# MAX96717_PINOUT.net
KiCad netlist of a schematic drawn in Altium Designer
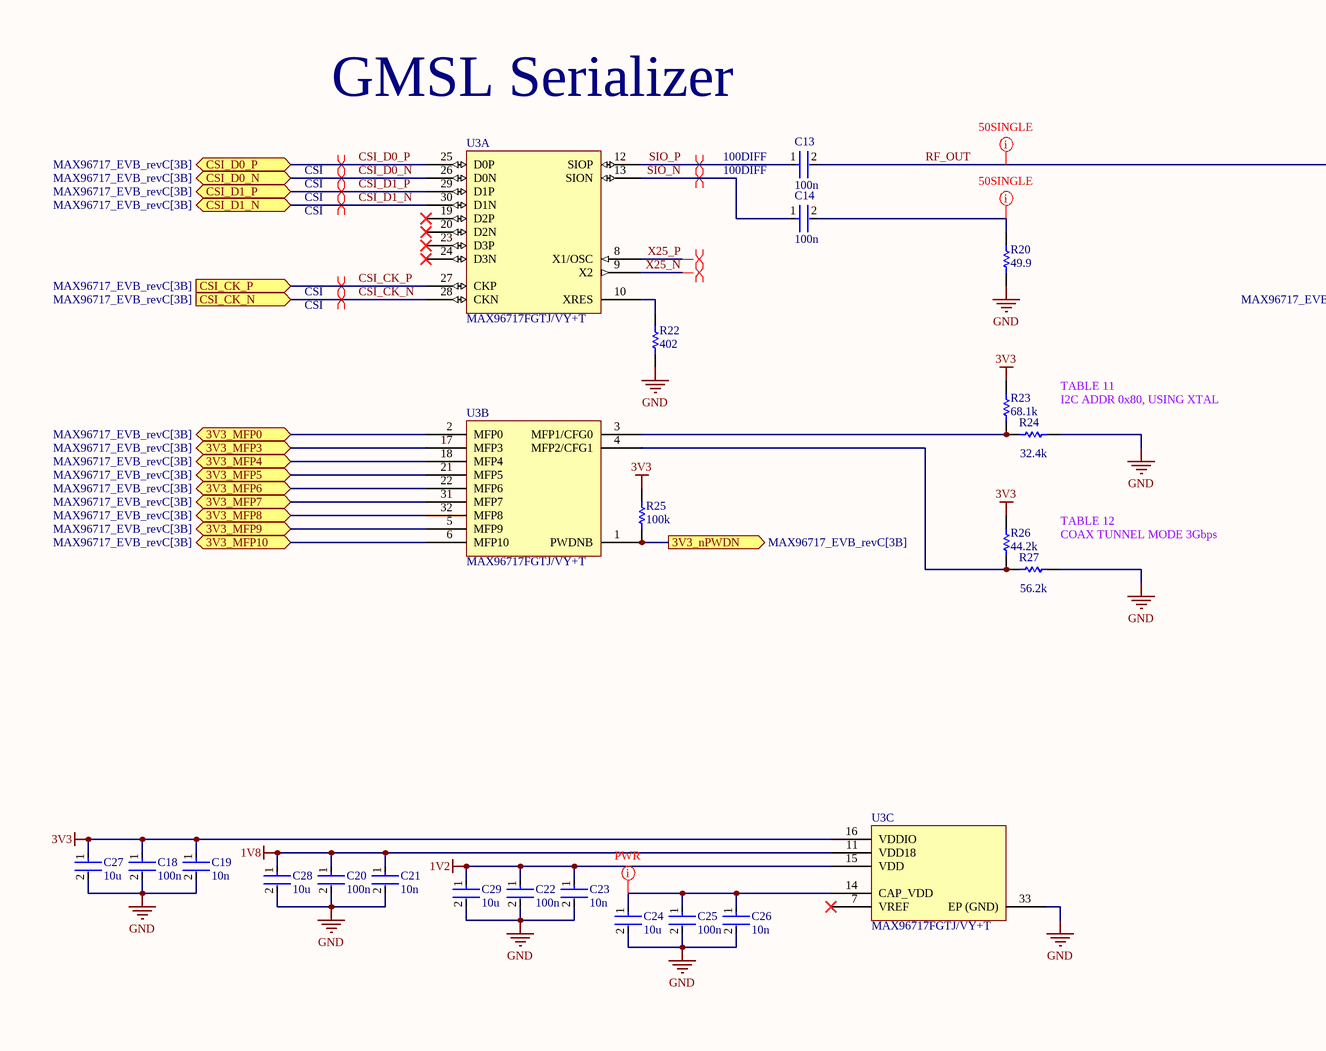
[diagram p0: MAX96717_PINOUT.SchDoc, left]
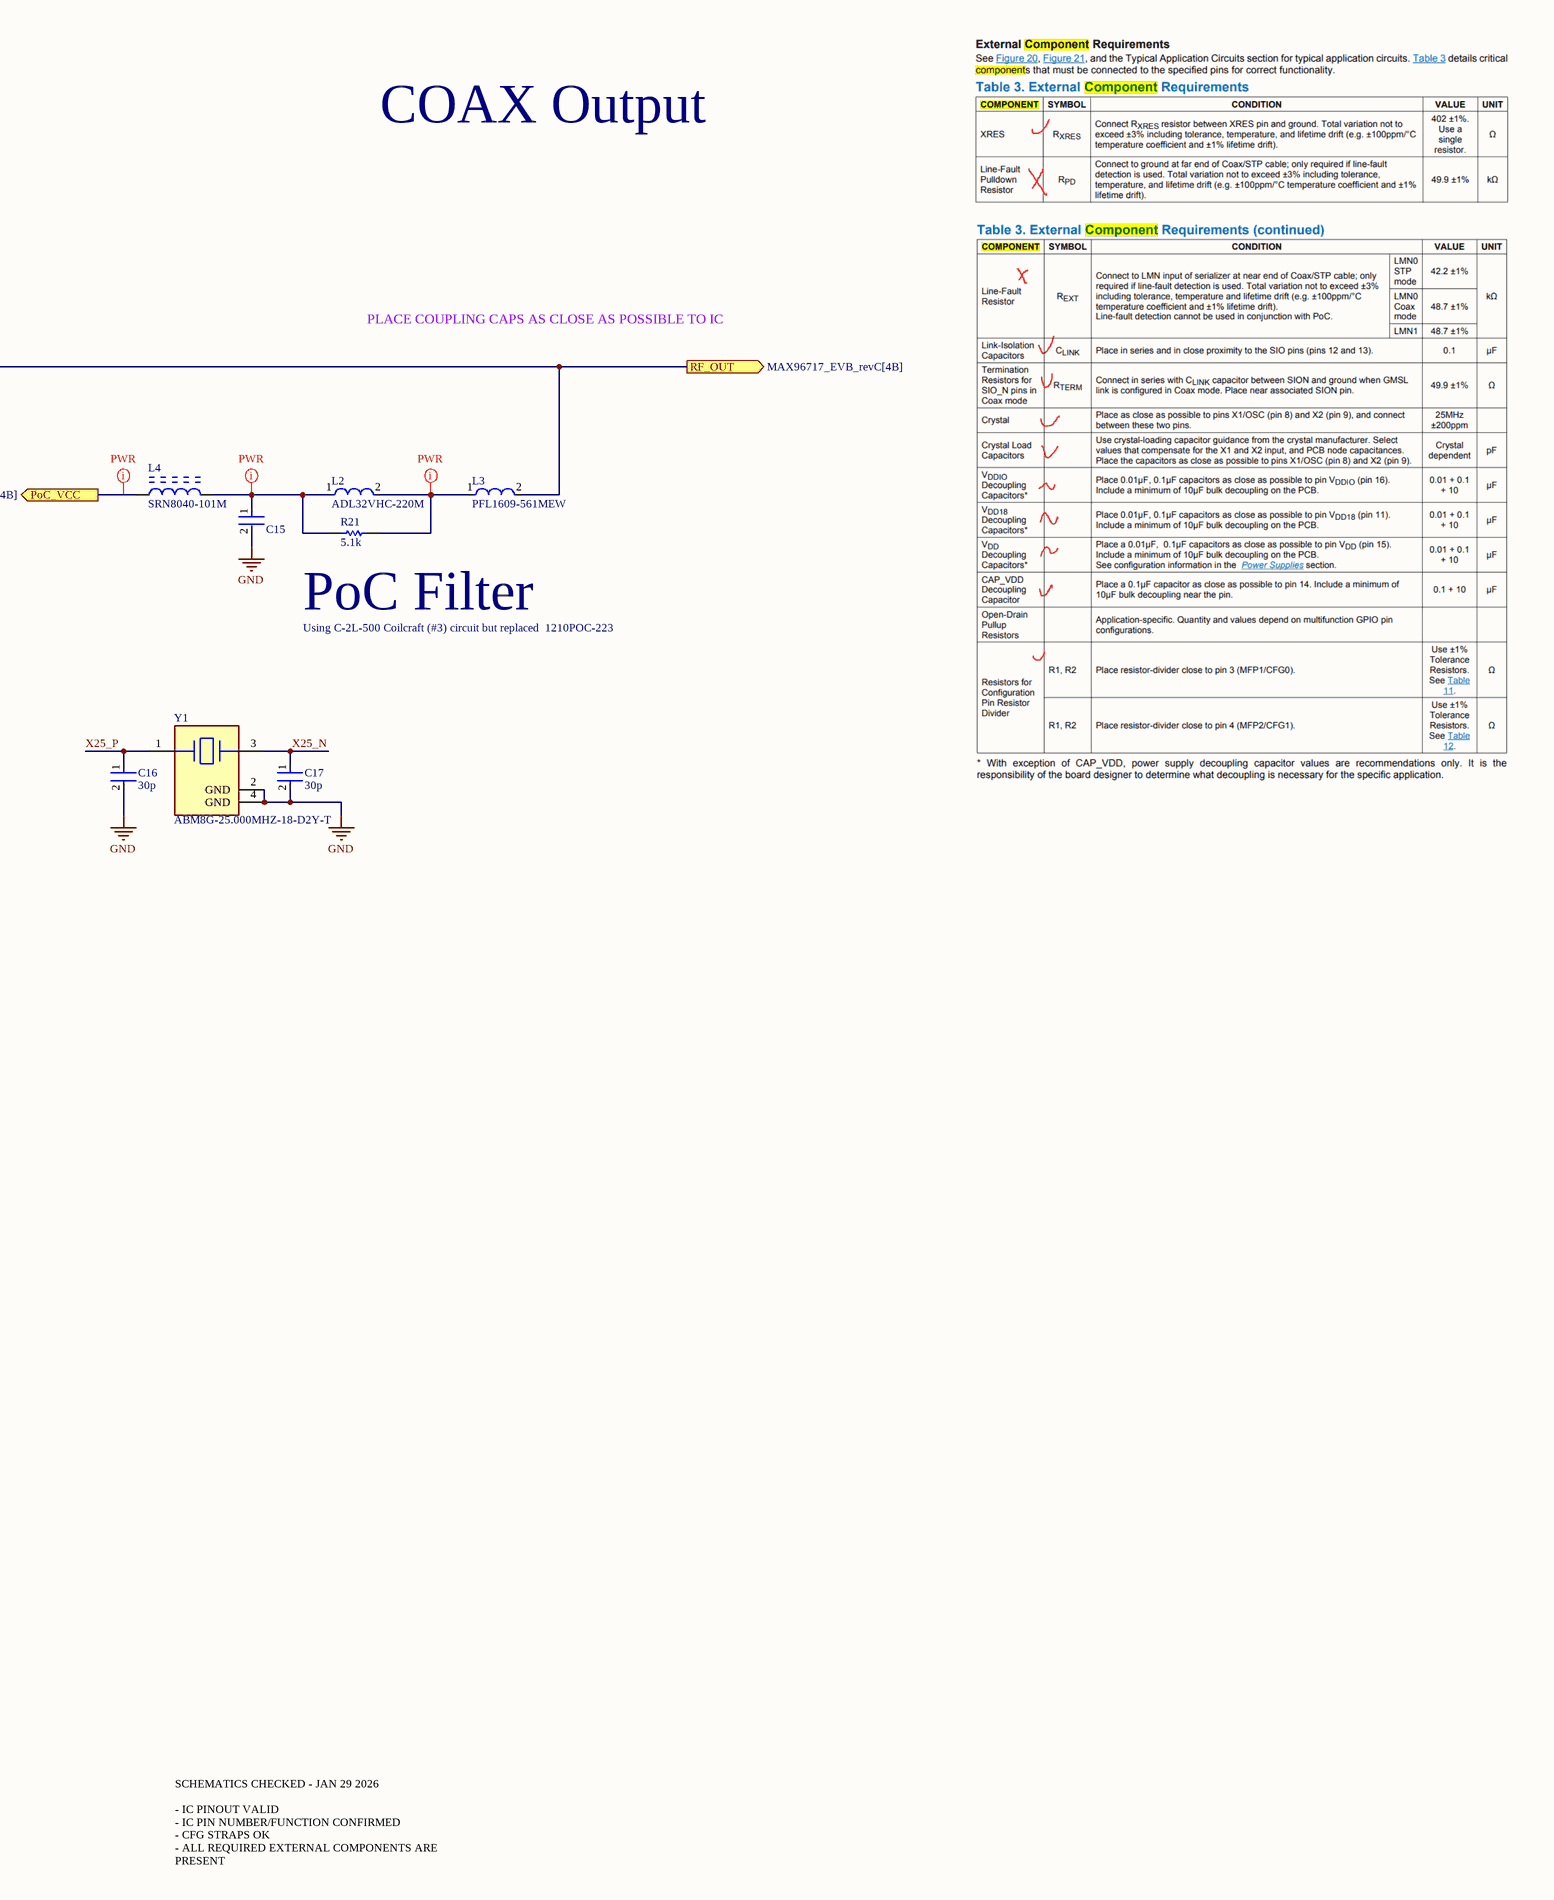
[diagram p1: MAX96717_PINOUT.SchDoc, right]

(export (version "E")
  (design (tool "Eeschema 10.0.6"))
  (components
    (comp (ref "C13")
      (value "100n")
      (footprint "FP-0402-L_1_0_0_05-W_0_5-IPC_A")
      (description "LARGE PADS, 0402 CAP, CHANGE COMMENT TO MATCH REAL P/N")
      (libsource (lib "Space Concordia") (part "b4654b650e69147ec39a6b967a45e02"))
    )
    (comp (ref "C14")
      (value "100n")
      (footprint "FP-0402-L_1_0_0_05-W_0_5-IPC_A")
      (description "LARGE PADS, 0402 CAP, CHANGE COMMENT TO MATCH REAL P/N")
      (libsource (lib "Space Concordia") (part "b4654b650e69147ec39a6b967a45e02"))
    )
    (comp (ref "C15")
      (value "GRM21BR61E226ME44L")
      (footprint "FP-GRM21B-0_2-e0_2_0_7-IPC_B")
      (description "Chip Multilayer Ceramic Capacitors for General Purpose, 0805, 22uF, X5R, 15%, 20%, 25V")
      (fields (field (name "TOLERANCE") "20%") (field (name "VOLTAGE") "25V"))
      (libsource (lib "Altium Content Vault") (part "b4654b650e69147ec39a6b967a45e02"))
    )
    (comp (ref "C16")
      (value "30p")
      (footprint "FP-0402-L_1_0_0_05-W_0_5-IPC_A")
      (description "LARGE PADS, 0402 CAP, CHANGE COMMENT TO MATCH REAL P/N")
      (libsource (lib "Space Concordia") (part "b4654b650e69147ec39a6b967a45e02"))
    )
    (comp (ref "C17")
      (value "30p")
      (footprint "FP-0402-L_1_0_0_05-W_0_5-IPC_A")
      (description "LARGE PADS, 0402 CAP, CHANGE COMMENT TO MATCH REAL P/N")
      (libsource (lib "Space Concordia") (part "b4654b650e69147ec39a6b967a45e02"))
    )
    (comp (ref "C18")
      (value "100n")
      (footprint "FP-0402-L_1_0_0_05-W_0_5-IPC_A")
      (description "LARGE PADS, 0402 CAP, CHANGE COMMENT TO MATCH REAL P/N")
      (libsource (lib "Space Concordia") (part "b4654b650e69147ec39a6b967a45e02"))
    )
    (comp (ref "C19")
      (value "10n")
      (footprint "FP-0402-L_1_0_0_05-W_0_5-IPC_A")
      (description "LARGE PADS, 0402 CAP, CHANGE COMMENT TO MATCH REAL P/N")
      (libsource (lib "Space Concordia") (part "b4654b650e69147ec39a6b967a45e02"))
    )
    (comp (ref "C20")
      (value "100n")
      (footprint "FP-0402-L_1_0_0_05-W_0_5-IPC_A")
      (description "LARGE PADS, 0402 CAP, CHANGE COMMENT TO MATCH REAL P/N")
      (libsource (lib "Space Concordia") (part "b4654b650e69147ec39a6b967a45e02"))
    )
    (comp (ref "C21")
      (value "10n")
      (footprint "FP-0402-L_1_0_0_05-W_0_5-IPC_A")
      (description "LARGE PADS, 0402 CAP, CHANGE COMMENT TO MATCH REAL P/N")
      (libsource (lib "Space Concordia") (part "b4654b650e69147ec39a6b967a45e02"))
    )
    (comp (ref "C22")
      (value "100n")
      (footprint "FP-0402-L_1_0_0_05-W_0_5-IPC_A")
      (description "LARGE PADS, 0402 CAP, CHANGE COMMENT TO MATCH REAL P/N")
      (libsource (lib "Space Concordia") (part "b4654b650e69147ec39a6b967a45e02"))
    )
    (comp (ref "C23")
      (value "10n")
      (footprint "FP-0402-L_1_0_0_05-W_0_5-IPC_A")
      (description "LARGE PADS, 0402 CAP, CHANGE COMMENT TO MATCH REAL P/N")
      (libsource (lib "Space Concordia") (part "b4654b650e69147ec39a6b967a45e02"))
    )
    (comp (ref "C24")
      (value "10u")
      (footprint "FP-0402-L_1_0_0_05-W_0_5-IPC_A")
      (description "LARGE PADS, 0402 CAP, CHANGE COMMENT TO MATCH REAL P/N")
      (libsource (lib "Space Concordia") (part "b4654b650e69147ec39a6b967a45e02"))
    )
    (comp (ref "C25")
      (value "100n")
      (footprint "FP-0402-L_1_0_0_05-W_0_5-IPC_A")
      (description "LARGE PADS, 0402 CAP, CHANGE COMMENT TO MATCH REAL P/N")
      (libsource (lib "Space Concordia") (part "b4654b650e69147ec39a6b967a45e02"))
    )
    (comp (ref "C26")
      (value "10n")
      (footprint "FP-0402-L_1_0_0_05-W_0_5-IPC_A")
      (description "LARGE PADS, 0402 CAP, CHANGE COMMENT TO MATCH REAL P/N")
      (libsource (lib "Space Concordia") (part "b4654b650e69147ec39a6b967a45e02"))
    )
    (comp (ref "C27")
      (value "10u")
      (footprint "FP-0402-L_1_0_0_05-W_0_5-IPC_A")
      (description "LARGE PADS, 0402 CAP, CHANGE COMMENT TO MATCH REAL P/N")
      (libsource (lib "Space Concordia") (part "b4654b650e69147ec39a6b967a45e02"))
    )
    (comp (ref "C28")
      (value "10u")
      (footprint "FP-0402-L_1_0_0_05-W_0_5-IPC_A")
      (description "LARGE PADS, 0402 CAP, CHANGE COMMENT TO MATCH REAL P/N")
      (libsource (lib "Space Concordia") (part "b4654b650e69147ec39a6b967a45e02"))
    )
    (comp (ref "C29")
      (value "10u")
      (footprint "FP-0402-L_1_0_0_05-W_0_5-IPC_A")
      (description "LARGE PADS, 0402 CAP, CHANGE COMMENT TO MATCH REAL P/N")
      (libsource (lib "Space Concordia") (part "b4654b650e69147ec39a6b967a45e02"))
    )
    (comp (ref "L2")
      (value "ADL32VHC-220M")
      (footprint "FP-1210POC-MFG")
      (description "NOT COILCRAFT - ACTUAL P# --> ADL32VHC-220M\r\n - Power Injection Chokes for PoC")
      (fields
        (field (name "MANUFACTURER") "coilcraft")
        (field (name "OCTOPART") "https://octopart.com/1210poc-223mrc-coilcraft-103207315")
      )
      (libsource (lib "Altium Content Vault") (part "725321dda6339637d4d059423bc1c3c"))
    )
    (comp (ref "L3")
      (value "PFL1609-561MEW")
      (footprint "FP-PFL1609-MFG")
      (description "Fixed Inductors PFL1609 Low Profile 0.56 uH 20 % 1.4 A")
      (fields (field (name "MANUFACTURER") "coilcraft") (field (name "TOLERANCE") "20%"))
      (libsource (lib "Altium Content Vault") (part "725321dda6339637d4d059423bc1c3c"))
    )
    (comp (ref "L4")
      (value "SRN8040-101M")
      (footprint "BOUR-SRN8040-101M_V")
      (description "Semi-Shielded Power Inductor, 100 uH, -40 to 125 degC, 2-Pin SMD, RoHS, Tape and Reel")
      (fields (field (name "TOLERANCE") "±20\r\n\r\n%") (field (name "MANUFACTURER") "Bourns"))
      (libsource (lib "Altium Content Vault") (part "IND-FERR-2"))
    )
    (comp (ref "R20")
      (value "49.9")
      (footprint "R0603B")
      (description "Resistor")
      (libsource (lib "Space Concordia") (part "Resistor"))
    )
    (comp (ref "R21")
      (value "5.1k")
      (footprint "R0603B")
      (description "Resistor")
      (libsource (lib "Space Concordia") (part "Resistor"))
    )
    (comp (ref "R22")
      (value "402")
      (footprint "R0603B")
      (description "Resistor")
      (libsource (lib "Space Concordia") (part "Resistor"))
    )
    (comp (ref "R23")
      (value "68.1k")
      (footprint "R0603B")
      (description "Resistor")
      (libsource (lib "Space Concordia") (part "Resistor"))
    )
    (comp (ref "R24")
      (value "32.4k")
      (footprint "R0603B")
      (description "Resistor")
      (libsource (lib "Space Concordia") (part "Resistor"))
    )
    (comp (ref "R25")
      (value "100k")
      (footprint "R0603B")
      (description "Resistor")
      (libsource (lib "Space Concordia") (part "Resistor"))
    )
    (comp (ref "R26")
      (value "44.2k")
      (footprint "R0603B")
      (description "Resistor")
      (libsource (lib "Space Concordia") (part "Resistor"))
    )
    (comp (ref "R27")
      (value "56.2k")
      (footprint "R0603B")
      (description "Resistor")
      (libsource (lib "Space Concordia") (part "Resistor"))
    )
    (comp (ref "U3")
      (value "MAX96717FGTJ/VY+T")
      (footprint "QFN50P500X500X80_HS-33N")
      (description "3Gbps Serializer TQFN-32 Serializers / Deserializers ROHS")
      (libsource (lib "Space Concordia") (part "MAX96717FGTJ_VY+T"))
    )
    (comp (ref "Y1")
      (value "ABM8G-25.000MHZ-18-D2Y-T")
      (footprint "FP-ABM8G-MFG")
      (description "Crystal 25MHz ±20ppm (Tol) ±30ppm (Stability) 18pF FUND 60Ω 4-Pin SMD T/R")
      (fields (field (name "TOLERANCE") "20ppm"))
      (libsource (lib "Altium Content Vault") (part "48e526d86b7f2615d98721063c72f49"))
    )
  )
  (nets
    (net (code "1") (name "/3V3_MFP0") (class "Default")
      (node (ref "U3") (pin "2") (pinfunction "MFP0_2") (pintype "passive"))
    )
    (net (code "2") (name "/3V3_MFP3") (class "Default")
      (node (ref "U3") (pin "17") (pinfunction "MFP3_17") (pintype "passive"))
    )
    (net (code "3") (name "/3V3_MFP4") (class "Default")
      (node (ref "U3") (pin "18") (pinfunction "MFP4_18") (pintype "passive"))
    )
    (net (code "4") (name "/3V3_MFP5") (class "Default")
      (node (ref "U3") (pin "21") (pinfunction "MFP5_21") (pintype "passive"))
    )
    (net (code "5") (name "/3V3_MFP6") (class "Default")
      (node (ref "U3") (pin "22") (pinfunction "MFP6_22") (pintype "passive"))
    )
    (net (code "6") (name "/3V3_MFP7") (class "Default")
      (node (ref "U3") (pin "31") (pinfunction "MFP7_31") (pintype "passive"))
    )
    (net (code "7") (name "/3V3_MFP8") (class "Default")
      (node (ref "U3") (pin "32") (pinfunction "MFP8_32") (pintype "passive"))
    )
    (net (code "8") (name "/3V3_MFP9") (class "Default")
      (node (ref "U3") (pin "5") (pinfunction "MFP9_5") (pintype "passive"))
    )
    (net (code "9") (name "/3V3_MFP10") (class "Default")
      (node (ref "U3") (pin "6") (pinfunction "MFP10_6") (pintype "passive"))
    )
    (net (code "10") (name "/3V3_nPWDN") (class "Default")
      (node (ref "R25") (pin "1") (pinfunction "1_1") (pintype "passive"))
      (node (ref "U3") (pin "1") (pinfunction "PWDNB_1") (pintype "passive"))
    )
    (net (code "11") (name "/CSI_CK_N") (class "Default")
      (node (ref "U3") (pin "28") (pinfunction "CKN_28") (pintype "bidirectional"))
    )
    (net (code "12") (name "/CSI_CK_P") (class "Default")
      (node (ref "U3") (pin "27") (pinfunction "CKP_27") (pintype "bidirectional"))
    )
    (net (code "13") (name "/CSI_D0_N") (class "Default")
      (node (ref "U3") (pin "26") (pinfunction "D0N_26") (pintype "bidirectional"))
    )
    (net (code "14") (name "/CSI_D0_P") (class "Default")
      (node (ref "U3") (pin "25") (pinfunction "D0P_25") (pintype "bidirectional"))
    )
    (net (code "15") (name "/CSI_D1_N") (class "Default")
      (node (ref "U3") (pin "30") (pinfunction "D1N_30") (pintype "bidirectional"))
    )
    (net (code "16") (name "/CSI_D1_P") (class "Default")
      (node (ref "U3") (pin "29") (pinfunction "D1P_29") (pintype "bidirectional"))
    )
    (net (code "17") (name "/PoC_VCC") (class "Default")
      (node (ref "L4") (pin "1") (pinfunction "1_1") (pintype "passive"))
    )
    (net (code "18") (name "/RF_OUT") (class "Default")
      (node (ref "C13") (pin "2") (pinfunction "2_2") (pintype "passive"))
      (node (ref "L3") (pin "2") (pinfunction "2_2") (pintype "passive"))
    )
    (net (code "19") (name "/SIO_N") (class "Default")
      (node (ref "C14") (pin "1") (pinfunction "1_1") (pintype "passive"))
      (node (ref "U3") (pin "13") (pinfunction "SION_13") (pintype "bidirectional"))
    )
    (net (code "20") (name "/SIO_P") (class "Default")
      (node (ref "C13") (pin "1") (pinfunction "1_1") (pintype "passive"))
      (node (ref "U3") (pin "12") (pinfunction "SIOP_12") (pintype "bidirectional"))
    )
    (net (code "21") (name "/X25_N") (class "Default")
      (node (ref "C17") (pin "1") (pinfunction "1_1") (pintype "passive"))
      (node (ref "U3") (pin "9") (pinfunction "X2_9") (pintype "output"))
      (node (ref "Y1") (pin "3") (pinfunction "3_3") (pintype "passive"))
    )
    (net (code "22") (name "/X25_P") (class "Default")
      (node (ref "C16") (pin "1") (pinfunction "1_1") (pintype "passive"))
      (node (ref "U3") (pin "8") (pinfunction "X1/OSC_8") (pintype "input"))
      (node (ref "Y1") (pin "1") (pinfunction "1_1") (pintype "passive"))
    )
    (net (code "23") (name "1V2") (class "Default")
      (node (ref "C22") (pin "1") (pinfunction "1_1") (pintype "passive"))
      (node (ref "C23") (pin "1") (pinfunction "1_1") (pintype "passive"))
      (node (ref "C29") (pin "1") (pinfunction "1_1") (pintype "passive"))
      (node (ref "U3") (pin "15") (pinfunction "VDD_15") (pintype "power_in"))
    )
    (net (code "24") (name "1V8") (class "Default")
      (node (ref "C20") (pin "1") (pinfunction "1_1") (pintype "passive"))
      (node (ref "C21") (pin "1") (pinfunction "1_1") (pintype "passive"))
      (node (ref "C28") (pin "1") (pinfunction "1_1") (pintype "passive"))
      (node (ref "U3") (pin "11") (pinfunction "VDD18_11") (pintype "power_in"))
    )
    (net (code "25") (name "3V3") (class "Default")
      (node (ref "C18") (pin "1") (pinfunction "1_1") (pintype "passive"))
      (node (ref "C19") (pin "1") (pinfunction "1_1") (pintype "passive"))
      (node (ref "C27") (pin "1") (pinfunction "1_1") (pintype "passive"))
      (node (ref "R23") (pin "2") (pinfunction "2_2") (pintype "passive"))
      (node (ref "R25") (pin "2") (pinfunction "2_2") (pintype "passive"))
      (node (ref "R26") (pin "2") (pinfunction "2_2") (pintype "passive"))
      (node (ref "U3") (pin "16") (pinfunction "VDDIO_16") (pintype "power_in"))
    )
    (net (code "26") (name "GND") (class "Default")
      (node (ref "C15") (pin "2") (pinfunction "2_2") (pintype "passive"))
      (node (ref "C16") (pin "2") (pinfunction "2_2") (pintype "passive"))
      (node (ref "C17") (pin "2") (pinfunction "2_2") (pintype "passive"))
      (node (ref "C18") (pin "2") (pinfunction "2_2") (pintype "passive"))
      (node (ref "C19") (pin "2") (pinfunction "2_2") (pintype "passive"))
      (node (ref "C20") (pin "2") (pinfunction "2_2") (pintype "passive"))
      (node (ref "C21") (pin "2") (pinfunction "2_2") (pintype "passive"))
      (node (ref "C22") (pin "2") (pinfunction "2_2") (pintype "passive"))
      (node (ref "C23") (pin "2") (pinfunction "2_2") (pintype "passive"))
      (node (ref "C24") (pin "2") (pinfunction "2_2") (pintype "passive"))
      (node (ref "C25") (pin "2") (pinfunction "2_2") (pintype "passive"))
      (node (ref "C26") (pin "2") (pinfunction "2_2") (pintype "passive"))
      (node (ref "C27") (pin "2") (pinfunction "2_2") (pintype "passive"))
      (node (ref "C28") (pin "2") (pinfunction "2_2") (pintype "passive"))
      (node (ref "C29") (pin "2") (pinfunction "2_2") (pintype "passive"))
      (node (ref "R20") (pin "1") (pinfunction "1_1") (pintype "passive"))
      (node (ref "R22") (pin "1") (pinfunction "1_1") (pintype "passive"))
      (node (ref "R24") (pin "1") (pinfunction "1_1") (pintype "passive"))
      (node (ref "R27") (pin "1") (pinfunction "1_1") (pintype "passive"))
      (node (ref "U3") (pin "33") (pinfunction "EP_(GND)_33") (pintype "power_in"))
      (node (ref "Y1") (pin "2") (pinfunction "GND_2") (pintype "power_in"))
      (node (ref "Y1") (pin "4") (pinfunction "GND_4") (pintype "power_in"))
    )
    (net (code "27") (name "Net-(C14-Pad2)") (class "Default")
      (node (ref "C14") (pin "2") (pinfunction "2_2") (pintype "passive"))
      (node (ref "R20") (pin "2") (pinfunction "2_2") (pintype "passive"))
    )
    (net (code "28") (name "Net-(C15-Pad1)") (class "Default")
      (node (ref "C15") (pin "1") (pinfunction "1_1") (pintype "passive"))
      (node (ref "L2") (pin "1") (pinfunction "1_1") (pintype "passive"))
      (node (ref "L4") (pin "2") (pinfunction "2_2") (pintype "passive"))
      (node (ref "R21") (pin "2") (pinfunction "2_2") (pintype "passive"))
    )
    (net (code "29") (name "Net-(L2-Pad2)") (class "Default")
      (node (ref "L2") (pin "2") (pinfunction "2_2") (pintype "passive"))
      (node (ref "L3") (pin "1") (pinfunction "1_1") (pintype "passive"))
      (node (ref "R21") (pin "1") (pinfunction "1_1") (pintype "passive"))
    )
    (net (code "30") (name "Net-(U3A-XRES)") (class "Default")
      (node (ref "R22") (pin "2") (pinfunction "2_2") (pintype "passive"))
      (node (ref "U3") (pin "10") (pinfunction "XRES_10") (pintype "passive"))
    )
    (net (code "31") (name "Net-(U3B-MFP1{slash}CFG0)") (class "Default")
      (node (ref "R23") (pin "1") (pinfunction "1_1") (pintype "passive"))
      (node (ref "R24") (pin "2") (pinfunction "2_2") (pintype "passive"))
      (node (ref "U3") (pin "3") (pinfunction "MFP1/CFG0_3") (pintype "passive"))
    )
    (net (code "32") (name "Net-(U3B-MFP2{slash}CFG1)") (class "Default")
      (node (ref "R26") (pin "1") (pinfunction "1_1") (pintype "passive"))
      (node (ref "R27") (pin "2") (pinfunction "2_2") (pintype "passive"))
      (node (ref "U3") (pin "4") (pinfunction "MFP2/CFG1_4") (pintype "passive"))
    )
    (net (code "33") (name "Net-(U3C-CAP_VDD)") (class "Default")
      (node (ref "C24") (pin "1") (pinfunction "1_1") (pintype "passive"))
      (node (ref "C25") (pin "1") (pinfunction "1_1") (pintype "passive"))
      (node (ref "C26") (pin "1") (pinfunction "1_1") (pintype "passive"))
      (node (ref "U3") (pin "14") (pinfunction "CAP_VDD_14") (pintype "power_in"))
    )
    (net (code "34") (name "unconnected-(U3A-D2N-Pad20)") (class "Default")
      (node (ref "U3") (pin "20") (pinfunction "D2N_20") (pintype "bidirectional+no_connect"))
    )
    (net (code "35") (name "unconnected-(U3A-D2P-Pad19)") (class "Default")
      (node (ref "U3") (pin "19") (pinfunction "D2P_19") (pintype "bidirectional+no_connect"))
    )
    (net (code "36") (name "unconnected-(U3A-D3N-Pad24)") (class "Default")
      (node (ref "U3") (pin "24") (pinfunction "D3N_24") (pintype "bidirectional+no_connect"))
    )
    (net (code "37") (name "unconnected-(U3A-D3P-Pad23)") (class "Default")
      (node (ref "U3") (pin "23") (pinfunction "D3P_23") (pintype "bidirectional+no_connect"))
    )
    (net (code "38") (name "unconnected-(U3C-VREF-Pad7)") (class "Default")
      (node (ref "U3") (pin "7") (pinfunction "VREF_7") (pintype "power_in+no_connect"))
    )
  )
)
